# ACCEL.net
KiCad netlist of a schematic drawn in Altium Designer
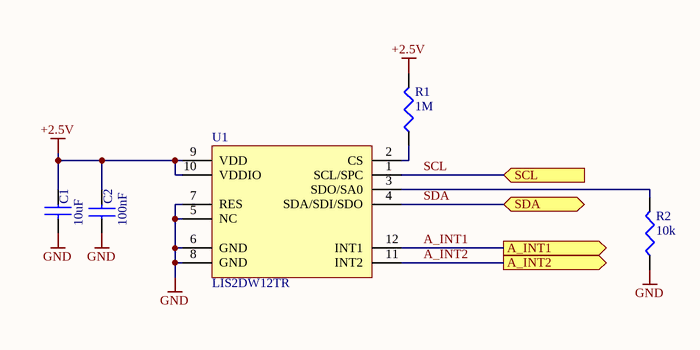
[diagram p0: ACCEL.SchDoc]

(export (version "E")
  (design (tool "Eeschema 10.0.6"))
  (components
    (comp (ref "C1")
      (value "10uF")
      (footprint "CAP0603")
      (description "Cap Ceramic 10uF 10V X5R 10% SMD 0603 85C Paper T/R")
      (fields
        (field (name "MANUFACTURER") "Samsung")
        (field (name "MANUFACTURER PART NUMBER") "CL10A106KP8NNNC")
      )
      (libsource (lib "Passive") (part "C - 10uF/10V"))
    )
    (comp (ref "C2")
      (value "100nF")
      (footprint "CAP0402")
      (fields
        (field (name "MANUFACTURER") "Multicomp")
        (field (name "MANUFACTURER PART NUMBER") "MC0402X104J160CT")
        (field (name "TOLERANCE") "5%")
      )
      (libsource (lib "Passive") (part "C - 100nF/0402"))
    )
    (comp (ref "R1")
      (value "1M")
      (footprint "RES0402")
      (description "MCMR04X1004FTL RES, 1M, 1%, 0.0625W, 0402, THICK FILM")
      (fields
        (field (name "MANUFACTURER") "MULTICOMP")
        (field (name "MANUFACTURER PART NUMBER") "MC0063W060311M")
      )
      (libsource (lib "Passive") (part "R - 1M/0402"))
    )
    (comp (ref "R2")
      (value "10k")
      (footprint "RES0402")
      (fields
        (field (name "MANUFACTURER") "Multicomp")
        (field (name "MANUFACTURER PART NUMBER") "MCWR04X1002FTL")
        (field (name "TOLERANCE") "1%")
      )
      (libsource (lib "Passive") (part "R - 10k/0402"))
    )
    (comp (ref "U1")
      (value "LIS2DW12TR")
      (footprint "LGA-12")
      (description "MEMS Accelerometer, Digital, X, Y, Z, ± 2g, ± 4g, ± 8g, ± 16g, 1.62 V, 3.6 V")
      (fields
        (field (name "MANUFACTURER") "TDK InvenSense")
        (field (name "MANUFACTURER PART NUMBER") "MPU-9250")
      )
      (libsource (lib "Active") (part "SEN - LIS2DW12TR"))
    )
  )
  (nets
    (net (code "1") (name "+2.5V") (class "Default")
      (node (ref "C1") (pin "1") (pinfunction "1_1") (pintype "passive"))
      (node (ref "C2") (pin "2") (pinfunction "2_2") (pintype "passive"))
      (node (ref "R1") (pin "2") (pinfunction "2_2") (pintype "passive"))
      (node (ref "U1") (pin "10") (pinfunction "VDDIO_10") (pintype "passive"))
      (node (ref "U1") (pin "9") (pinfunction "VDD_9") (pintype "passive"))
    )
    (net (code "2") (name "/A_INT1") (class "Default")
      (node (ref "U1") (pin "12") (pinfunction "INT1_12") (pintype "passive"))
    )
    (net (code "3") (name "/A_INT2") (class "Default")
      (node (ref "U1") (pin "11") (pinfunction "INT2_11") (pintype "passive"))
    )
    (net (code "4") (name "/SCL") (class "Default")
      (node (ref "U1") (pin "1") (pinfunction "SCL/SPC_1") (pintype "passive"))
    )
    (net (code "5") (name "/SDA") (class "Default")
      (node (ref "U1") (pin "4") (pinfunction "SDA/SDI/SDO_4") (pintype "passive"))
    )
    (net (code "6") (name "GND") (class "Default")
      (node (ref "C1") (pin "2") (pinfunction "2_2") (pintype "passive"))
      (node (ref "C2") (pin "1") (pinfunction "1_1") (pintype "passive"))
      (node (ref "R2") (pin "1") (pinfunction "1_1") (pintype "passive"))
      (node (ref "U1") (pin "5") (pinfunction "NC_5") (pintype "passive"))
      (node (ref "U1") (pin "6") (pinfunction "GND_6") (pintype "passive"))
      (node (ref "U1") (pin "7") (pinfunction "RES_7") (pintype "passive"))
      (node (ref "U1") (pin "8") (pinfunction "GND_8") (pintype "passive"))
    )
    (net (code "7") (name "Net-(U1-CS)") (class "Default")
      (node (ref "R1") (pin "1") (pinfunction "1_1") (pintype "passive"))
      (node (ref "U1") (pin "2") (pinfunction "CS_2") (pintype "passive"))
    )
    (net (code "8") (name "Net-(U1-SDO{slash}SA0)") (class "Default")
      (node (ref "R2") (pin "2") (pinfunction "2_2") (pintype "passive"))
      (node (ref "U1") (pin "3") (pinfunction "SDO/SA0_3") (pintype "passive"))
    )
  )
)
